# ElectricalOutlet.net
KiCad netlist of a schematic drawn in EAGLE
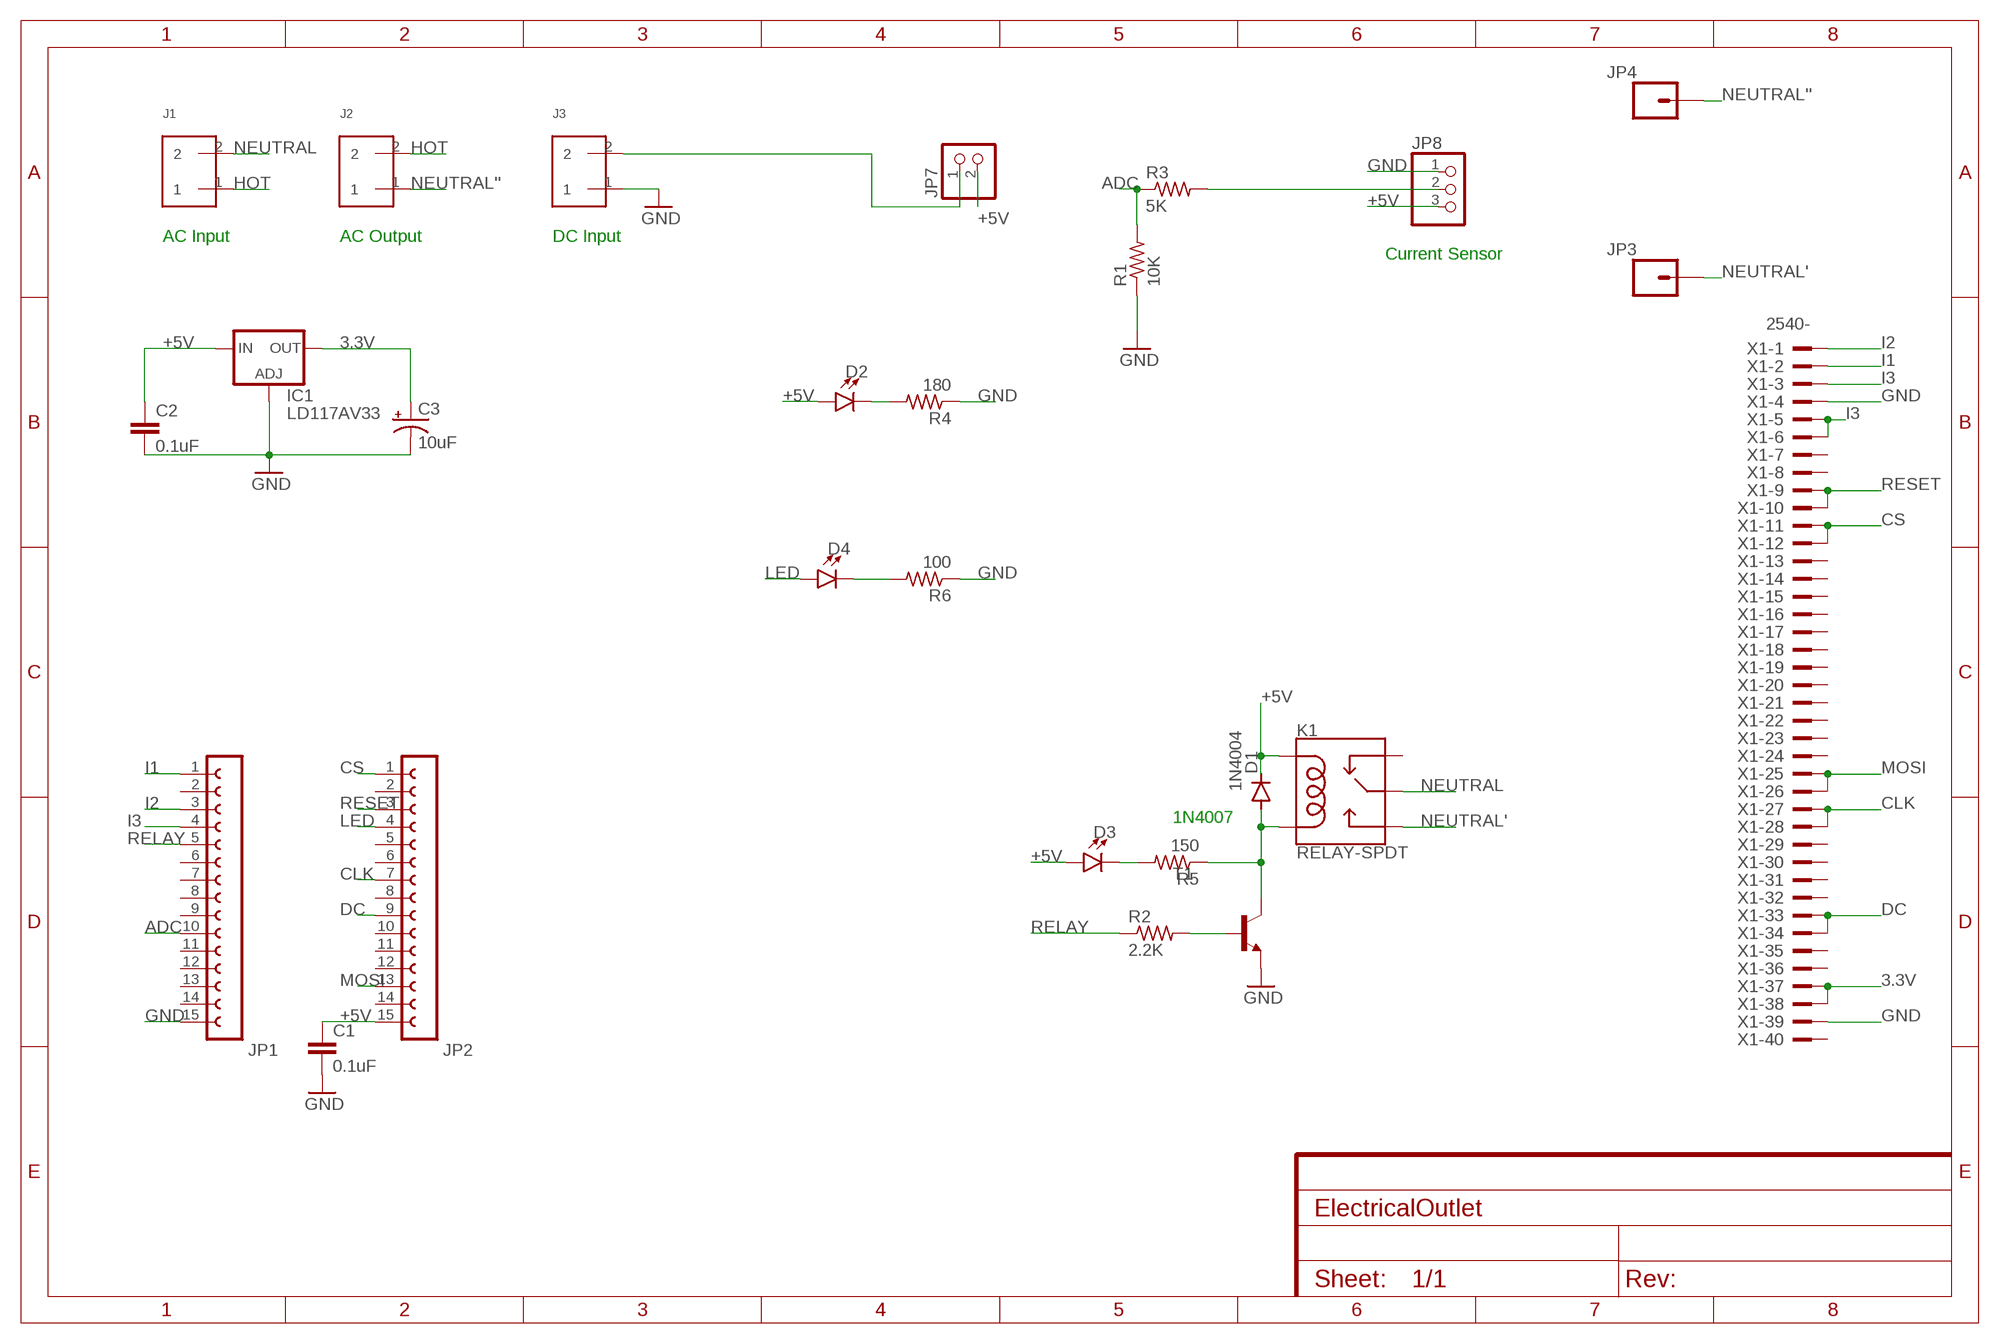
[diagram p0: schematic, sheet 1]

(export (version "E")
  (design (tool "Eeschema 10.0.6"))
  (components
    (comp (ref "C1")
      (value "0.1uF")
      (footprint "eagle-import:CAP-PTH-SMALL-KIT")
      (libsource (lib "eagle-import") (part "0.1UF-KIT-EZ-50V-20%"))
    )
    (comp (ref "C2")
      (value "0.1uF")
      (footprint "eagle-import:CAP-PTH-SMALL-KIT")
      (libsource (lib "eagle-import") (part "0.1UF-KIT-EZ-50V-20%"))
    )
    (comp (ref "C3")
      (value "10uF")
      (footprint "eagle-import:CPOL-RADIAL-2.5MM-5MM-KIT")
      (libsource (lib "eagle-import") (part "10UF-POLAR-RADIAL-2.5MM-KIT-25V-20%"))
    )
    (comp (ref "D1")
      (value "1N4004")
      (footprint "eagle-import:DO41-10")
      (libsource (lib "eagle-import") (part "1N4004"))
    )
    (comp (ref "D2")
      (value "LED3MM")
      (footprint "eagle-import:LED_3MM")
      (libsource (lib "eagle-import") (part "LED3MM"))
    )
    (comp (ref "D3")
      (value "LED3MM")
      (footprint "eagle-import:LED_3MM")
      (libsource (lib "eagle-import") (part "LED3MM"))
    )
    (comp (ref "D4")
      (value "LED3MM")
      (footprint "eagle-import:LED_3MM")
      (libsource (lib "eagle-import") (part "LED3MM"))
    )
    (comp (ref "IC1")
      (value "LD117AV33")
      (footprint "eagle-import:TO220L1")
      (libsource (lib "eagle-import") (part "LD117A?V33"))
    )
    (comp (ref "J1")
      (value "SCREW_TERMINAL")
      (footprint "eagle-import:PHEONIX-1935161")
      (libsource (lib "eagle-import") (part "SCREW_TERMINAL"))
    )
    (comp (ref "J2")
      (value "SCREW_TERMINAL")
      (footprint "eagle-import:PHEONIX-1935161")
      (libsource (lib "eagle-import") (part "SCREW_TERMINAL"))
    )
    (comp (ref "J3")
      (value "SCREW_TERMINAL")
      (footprint "eagle-import:PHEONIX-1935161")
      (libsource (lib "eagle-import") (part "SCREW_TERMINAL"))
    )
    (comp (ref "JP1")
      (value "FE15-1")
      (footprint "eagle-import:FE15")
      (libsource (lib "eagle-import") (part "FE15-1"))
    )
    (comp (ref "JP2")
      (value "FE15-1")
      (footprint "eagle-import:FE15")
      (libsource (lib "eagle-import") (part "FE15-1"))
    )
    (comp (ref "JP3")
      (value "CONN_01")
      (footprint "eagle-import:1X01")
      (libsource (lib "eagle-import") (part "CONN_01"))
    )
    (comp (ref "JP4")
      (value "CONN_01")
      (footprint "eagle-import:1X01")
      (libsource (lib "eagle-import") (part "CONN_01"))
    )
    (comp (ref "JP7")
      (value "PINHD-1X2")
      (footprint "eagle-import:1X02")
      (libsource (lib "eagle-import") (part "PINHD-1X2"))
    )
    (comp (ref "JP8")
      (value "PINHD-1X3")
      (footprint "eagle-import:1X03")
      (libsource (lib "eagle-import") (part "PINHD-1X3"))
    )
    (comp (ref "K1")
      (value "RELAY-SPDT")
      (footprint "eagle-import:RELAY_G5LE")
      (libsource (lib "eagle-import") (part "RELAY-SPDT"))
    )
    (comp (ref "R1")
      (value "10K")
      (footprint "eagle-import:0204_7")
      (libsource (lib "eagle-import") (part "R-US_0204/7"))
    )
    (comp (ref "R2")
      (value "2.2K")
      (footprint "eagle-import:0204_7")
      (libsource (lib "eagle-import") (part "R-US_0204/7"))
    )
    (comp (ref "R3")
      (value "5K")
      (footprint "eagle-import:0204_7")
      (libsource (lib "eagle-import") (part "R-US_0204/7"))
    )
    (comp (ref "R4")
      (value "180")
      (footprint "eagle-import:0204_7")
      (libsource (lib "eagle-import") (part "R-US_0204/7"))
    )
    (comp (ref "R5")
      (value "150")
      (footprint "eagle-import:0204_7")
      (libsource (lib "eagle-import") (part "R-US_0204/7"))
    )
    (comp (ref "R6")
      (value "100")
      (footprint "eagle-import:0204_7")
      (libsource (lib "eagle-import") (part "R-US_0204/7"))
    )
    (comp (ref "T1")
      (value "-NPN-TO92")
      (footprint "eagle-import:TO92")
      (libsource (lib "eagle-import") (part "-NPN-TO92"))
    )
    (comp (ref "X1")
      (value "2540-")
      (footprint "eagle-import:PAK100_2500-40")
      (libsource (lib "eagle-import") (part "2540-"))
    )
  )
  (nets
    (net (code "1") (name "/+5V") (class "Default")
      (node (ref "C1") (pin "1") (pinfunction "1_1") (pintype "passive"))
      (node (ref "C2") (pin "1") (pinfunction "1_1") (pintype "passive"))
      (node (ref "D1") (pin "C") (pinfunction "C_C") (pintype "passive"))
      (node (ref "D2") (pin "A") (pinfunction "A_A") (pintype "passive"))
      (node (ref "D3") (pin "A") (pinfunction "A_A") (pintype "passive"))
      (node (ref "IC1") (pin "3") (pinfunction "IN_3") (pintype "input"))
      (node (ref "JP2") (pin "15") (pinfunction "15_15") (pintype "passive"))
      (node (ref "JP7") (pin "2") (pinfunction "2_2") (pintype "passive"))
      (node (ref "JP8") (pin "3") (pinfunction "3_3") (pintype "passive"))
      (node (ref "K1") (pin "2") (pinfunction "COIL1_2") (pintype "bidirectional"))
    )
    (net (code "2") (name "/3.3V") (class "Default")
      (node (ref "C3") (pin "1") (pinfunction "+_1") (pintype "passive"))
      (node (ref "IC1") (pin "2") (pinfunction "OUT_2") (pintype "passive"))
      (node (ref "X1") (pin "37") (pinfunction "KL_37") (pintype "passive"))
      (node (ref "X1") (pin "38") (pinfunction "KL_38") (pintype "passive"))
    )
    (net (code "3") (name "/ADC") (class "Default")
      (node (ref "JP1") (pin "10") (pinfunction "10_10") (pintype "passive"))
      (node (ref "R1") (pin "2") (pinfunction "2_2") (pintype "passive"))
      (node (ref "R3") (pin "1") (pinfunction "1_1") (pintype "passive"))
    )
    (net (code "4") (name "/CLK") (class "Default")
      (node (ref "JP2") (pin "7") (pinfunction "7_7") (pintype "passive"))
      (node (ref "X1") (pin "27") (pinfunction "KL_27") (pintype "passive"))
      (node (ref "X1") (pin "28") (pinfunction "KL_28") (pintype "passive"))
    )
    (net (code "5") (name "/CS") (class "Default")
      (node (ref "JP2") (pin "1") (pinfunction "1_1") (pintype "passive"))
      (node (ref "X1") (pin "11") (pinfunction "KL_11") (pintype "passive"))
      (node (ref "X1") (pin "12") (pinfunction "KL_12") (pintype "passive"))
    )
    (net (code "6") (name "/DC") (class "Default")
      (node (ref "JP2") (pin "9") (pinfunction "9_9") (pintype "passive"))
      (node (ref "X1") (pin "33") (pinfunction "KL_33") (pintype "passive"))
      (node (ref "X1") (pin "34") (pinfunction "KL_34") (pintype "passive"))
    )
    (net (code "7") (name "/HOT") (class "Default")
      (node (ref "J1") (pin "1") (pinfunction "1_1") (pintype "bidirectional"))
      (node (ref "J2") (pin "2") (pinfunction "2_2") (pintype "bidirectional"))
    )
    (net (code "8") (name "/I1") (class "Default")
      (node (ref "JP1") (pin "1") (pinfunction "1_1") (pintype "passive"))
      (node (ref "X1") (pin "2") (pinfunction "KL_2") (pintype "passive"))
    )
    (net (code "9") (name "/I2") (class "Default")
      (node (ref "JP1") (pin "3") (pinfunction "3_3") (pintype "passive"))
      (node (ref "X1") (pin "1") (pinfunction "KL_1") (pintype "passive"))
    )
    (net (code "10") (name "/I3") (class "Default")
      (node (ref "JP1") (pin "4") (pinfunction "4_4") (pintype "passive"))
      (node (ref "X1") (pin "3") (pinfunction "KL_3") (pintype "passive"))
      (node (ref "X1") (pin "5") (pinfunction "KL_5") (pintype "passive"))
      (node (ref "X1") (pin "6") (pinfunction "KL_6") (pintype "passive"))
    )
    (net (code "11") (name "/LED") (class "Default")
      (node (ref "D4") (pin "A") (pinfunction "A_A") (pintype "passive"))
      (node (ref "JP2") (pin "4") (pinfunction "4_4") (pintype "passive"))
    )
    (net (code "12") (name "/MOSI") (class "Default")
      (node (ref "JP2") (pin "13") (pinfunction "13_13") (pintype "passive"))
      (node (ref "X1") (pin "25") (pinfunction "KL_25") (pintype "passive"))
      (node (ref "X1") (pin "26") (pinfunction "KL_26") (pintype "passive"))
    )
    (net (code "13") (name "/NEUTRAL") (class "Default")
      (node (ref "J1") (pin "2") (pinfunction "2_2") (pintype "bidirectional"))
      (node (ref "K1") (pin "1") (pinfunction "MAIN_1") (pintype "bidirectional"))
    )
    (net (code "14") (name "/NEUTRAL'") (class "Default")
      (node (ref "JP3") (pin "1") (pinfunction "1_1") (pintype "passive"))
      (node (ref "K1") (pin "3") (pinfunction "NO_3") (pintype "bidirectional"))
    )
    (net (code "15") (name "/NEUTRAL''") (class "Default")
      (node (ref "J2") (pin "1") (pinfunction "1_1") (pintype "bidirectional"))
      (node (ref "JP4") (pin "1") (pinfunction "1_1") (pintype "passive"))
    )
    (net (code "16") (name "/RELAY") (class "Default")
      (node (ref "JP1") (pin "5") (pinfunction "5_5") (pintype "passive"))
      (node (ref "R2") (pin "1") (pinfunction "1_1") (pintype "passive"))
    )
    (net (code "17") (name "/RESET") (class "Default")
      (node (ref "JP2") (pin "3") (pinfunction "3_3") (pintype "passive"))
      (node (ref "X1") (pin "10") (pinfunction "KL_10") (pintype "passive"))
      (node (ref "X1") (pin "9") (pinfunction "KL_9") (pintype "passive"))
    )
    (net (code "18") (name "GND") (class "Default")
      (node (ref "C1") (pin "2") (pinfunction "2_2") (pintype "passive"))
      (node (ref "C2") (pin "2") (pinfunction "2_2") (pintype "passive"))
      (node (ref "C3") (pin "2") (pinfunction "-_2") (pintype "passive"))
      (node (ref "IC1") (pin "1") (pinfunction "ADJ_1") (pintype "input"))
      (node (ref "J3") (pin "1") (pinfunction "1_1") (pintype "bidirectional"))
      (node (ref "JP1") (pin "15") (pinfunction "15_15") (pintype "passive"))
      (node (ref "JP8") (pin "1") (pinfunction "1_1") (pintype "passive"))
      (node (ref "R1") (pin "1") (pinfunction "1_1") (pintype "passive"))
      (node (ref "R4") (pin "1") (pinfunction "1_1") (pintype "passive"))
      (node (ref "R6") (pin "1") (pinfunction "1_1") (pintype "passive"))
      (node (ref "T1") (pin "1") (pinfunction "E_1") (pintype "passive"))
      (node (ref "X1") (pin "39") (pinfunction "KL_39") (pintype "passive"))
      (node (ref "X1") (pin "4") (pinfunction "KL_4") (pintype "passive"))
    )
    (net (code "19") (name "Net-(D2-C)") (class "Default")
      (node (ref "D2") (pin "K") (pinfunction "C_K") (pintype "passive"))
      (node (ref "R4") (pin "2") (pinfunction "2_2") (pintype "passive"))
    )
    (net (code "20") (name "Net-(D3-C)") (class "Default")
      (node (ref "D3") (pin "K") (pinfunction "C_K") (pintype "passive"))
      (node (ref "R5") (pin "2") (pinfunction "2_2") (pintype "passive"))
    )
    (net (code "21") (name "Net-(D4-C)") (class "Default")
      (node (ref "D4") (pin "K") (pinfunction "C_K") (pintype "passive"))
      (node (ref "R6") (pin "2") (pinfunction "2_2") (pintype "passive"))
    )
    (net (code "22") (name "Net-(J3-Pad2)") (class "Default")
      (node (ref "J3") (pin "2") (pinfunction "2_2") (pintype "bidirectional"))
      (node (ref "JP7") (pin "1") (pinfunction "1_1") (pintype "passive"))
    )
    (net (code "23") (name "Net-(JP8-Pad2)") (class "Default")
      (node (ref "JP8") (pin "2") (pinfunction "2_2") (pintype "passive"))
      (node (ref "R3") (pin "2") (pinfunction "2_2") (pintype "passive"))
    )
    (net (code "24") (name "Net-(K1-COIL2)") (class "Default")
      (node (ref "D1") (pin "A") (pinfunction "A_A") (pintype "passive"))
      (node (ref "K1") (pin "5") (pinfunction "COIL2_5") (pintype "bidirectional"))
      (node (ref "R5") (pin "1") (pinfunction "1_1") (pintype "passive"))
      (node (ref "T1") (pin "3") (pinfunction "C_3") (pintype "passive"))
    )
    (net (code "25") (name "Net-(T1-B)") (class "Default")
      (node (ref "R2") (pin "2") (pinfunction "2_2") (pintype "passive"))
      (node (ref "T1") (pin "2") (pinfunction "B_2") (pintype "passive"))
    )
    (net (code "26") (name "unconnected-(JP1-Pad2)") (class "Default")
      (node (ref "JP1") (pin "2") (pinfunction "2_2") (pintype "passive"))
    )
    (net (code "27") (name "unconnected-(JP1-Pad6)") (class "Default")
      (node (ref "JP1") (pin "6") (pinfunction "6_6") (pintype "passive"))
    )
    (net (code "28") (name "unconnected-(JP1-Pad7)") (class "Default")
      (node (ref "JP1") (pin "7") (pinfunction "7_7") (pintype "passive"))
    )
    (net (code "29") (name "unconnected-(JP1-Pad8)") (class "Default")
      (node (ref "JP1") (pin "8") (pinfunction "8_8") (pintype "passive"))
    )
    (net (code "30") (name "unconnected-(JP1-Pad9)") (class "Default")
      (node (ref "JP1") (pin "9") (pinfunction "9_9") (pintype "passive"))
    )
    (net (code "31") (name "unconnected-(JP1-Pad11)") (class "Default")
      (node (ref "JP1") (pin "11") (pinfunction "11_11") (pintype "passive"))
    )
    (net (code "32") (name "unconnected-(JP1-Pad12)") (class "Default")
      (node (ref "JP1") (pin "12") (pinfunction "12_12") (pintype "passive"))
    )
    (net (code "33") (name "unconnected-(JP1-Pad13)") (class "Default")
      (node (ref "JP1") (pin "13") (pinfunction "13_13") (pintype "passive"))
    )
    (net (code "34") (name "unconnected-(JP1-Pad14)") (class "Default")
      (node (ref "JP1") (pin "14") (pinfunction "14_14") (pintype "passive"))
    )
    (net (code "35") (name "unconnected-(JP2-Pad2)") (class "Default")
      (node (ref "JP2") (pin "2") (pinfunction "2_2") (pintype "passive"))
    )
    (net (code "36") (name "unconnected-(JP2-Pad5)") (class "Default")
      (node (ref "JP2") (pin "5") (pinfunction "5_5") (pintype "passive"))
    )
    (net (code "37") (name "unconnected-(JP2-Pad6)") (class "Default")
      (node (ref "JP2") (pin "6") (pinfunction "6_6") (pintype "passive"))
    )
    (net (code "38") (name "unconnected-(JP2-Pad8)") (class "Default")
      (node (ref "JP2") (pin "8") (pinfunction "8_8") (pintype "passive"))
    )
    (net (code "39") (name "unconnected-(JP2-Pad10)") (class "Default")
      (node (ref "JP2") (pin "10") (pinfunction "10_10") (pintype "passive"))
    )
    (net (code "40") (name "unconnected-(JP2-Pad11)") (class "Default")
      (node (ref "JP2") (pin "11") (pinfunction "11_11") (pintype "passive"))
    )
    (net (code "41") (name "unconnected-(JP2-Pad12)") (class "Default")
      (node (ref "JP2") (pin "12") (pinfunction "12_12") (pintype "passive"))
    )
    (net (code "42") (name "unconnected-(JP2-Pad14)") (class "Default")
      (node (ref "JP2") (pin "14") (pinfunction "14_14") (pintype "passive"))
    )
    (net (code "43") (name "unconnected-(K1-NC-Pad4)") (class "Default")
      (node (ref "K1") (pin "4") (pinfunction "NC_4") (pintype "bidirectional"))
    )
    (net (code "44") (name "unconnected-(X1AC-KL-Pad35)") (class "Default")
      (node (ref "X1") (pin "35") (pinfunction "KL_35") (pintype "passive"))
    )
    (net (code "45") (name "unconnected-(X1AD-KL-Pad36)") (class "Default")
      (node (ref "X1") (pin "36") (pinfunction "KL_36") (pintype "passive"))
    )
    (net (code "46") (name "unconnected-(X1AI-KL-Pad40)") (class "Default")
      (node (ref "X1") (pin "40") (pinfunction "KL_40") (pintype "passive"))
    )
    (net (code "47") (name "unconnected-(X1AL-KL-Pad7)") (class "Default")
      (node (ref "X1") (pin "7") (pinfunction "KL_7") (pintype "passive"))
    )
    (net (code "48") (name "unconnected-(X1AM-KL-Pad8)") (class "Default")
      (node (ref "X1") (pin "8") (pinfunction "KL_8") (pintype "passive"))
    )
    (net (code "49") (name "unconnected-(X1E-KL-Pad13)") (class "Default")
      (node (ref "X1") (pin "13") (pinfunction "KL_13") (pintype "passive"))
    )
    (net (code "50") (name "unconnected-(X1F-KL-Pad14)") (class "Default")
      (node (ref "X1") (pin "14") (pinfunction "KL_14") (pintype "passive"))
    )
    (net (code "51") (name "unconnected-(X1G-KL-Pad15)") (class "Default")
      (node (ref "X1") (pin "15") (pinfunction "KL_15") (pintype "passive"))
    )
    (net (code "52") (name "unconnected-(X1H-KL-Pad16)") (class "Default")
      (node (ref "X1") (pin "16") (pinfunction "KL_16") (pintype "passive"))
    )
    (net (code "53") (name "unconnected-(X1I-KL-Pad17)") (class "Default")
      (node (ref "X1") (pin "17") (pinfunction "KL_17") (pintype "passive"))
    )
    (net (code "54") (name "unconnected-(X1J-KL-Pad18)") (class "Default")
      (node (ref "X1") (pin "18") (pinfunction "KL_18") (pintype "passive"))
    )
    (net (code "55") (name "unconnected-(X1K-KL-Pad19)") (class "Default")
      (node (ref "X1") (pin "19") (pinfunction "KL_19") (pintype "passive"))
    )
    (net (code "56") (name "unconnected-(X1M-KL-Pad20)") (class "Default")
      (node (ref "X1") (pin "20") (pinfunction "KL_20") (pintype "passive"))
    )
    (net (code "57") (name "unconnected-(X1N-KL-Pad21)") (class "Default")
      (node (ref "X1") (pin "21") (pinfunction "KL_21") (pintype "passive"))
    )
    (net (code "58") (name "unconnected-(X1O-KL-Pad22)") (class "Default")
      (node (ref "X1") (pin "22") (pinfunction "KL_22") (pintype "passive"))
    )
    (net (code "59") (name "unconnected-(X1P-KL-Pad23)") (class "Default")
      (node (ref "X1") (pin "23") (pinfunction "KL_23") (pintype "passive"))
    )
    (net (code "60") (name "unconnected-(X1Q-KL-Pad24)") (class "Default")
      (node (ref "X1") (pin "24") (pinfunction "KL_24") (pintype "passive"))
    )
    (net (code "61") (name "unconnected-(X1V-KL-Pad29)") (class "Default")
      (node (ref "X1") (pin "29") (pinfunction "KL_29") (pintype "passive"))
    )
    (net (code "62") (name "unconnected-(X1X-KL-Pad30)") (class "Default")
      (node (ref "X1") (pin "30") (pinfunction "KL_30") (pintype "passive"))
    )
    (net (code "63") (name "unconnected-(X1Y-KL-Pad31)") (class "Default")
      (node (ref "X1") (pin "31") (pinfunction "KL_31") (pintype "passive"))
    )
    (net (code "64") (name "unconnected-(X1Z-KL-Pad32)") (class "Default")
      (node (ref "X1") (pin "32") (pinfunction "KL_32") (pintype "passive"))
    )
  )
)
